# Voltage_Source.net
KiCad netlist of a schematic drawn in Altium Designer
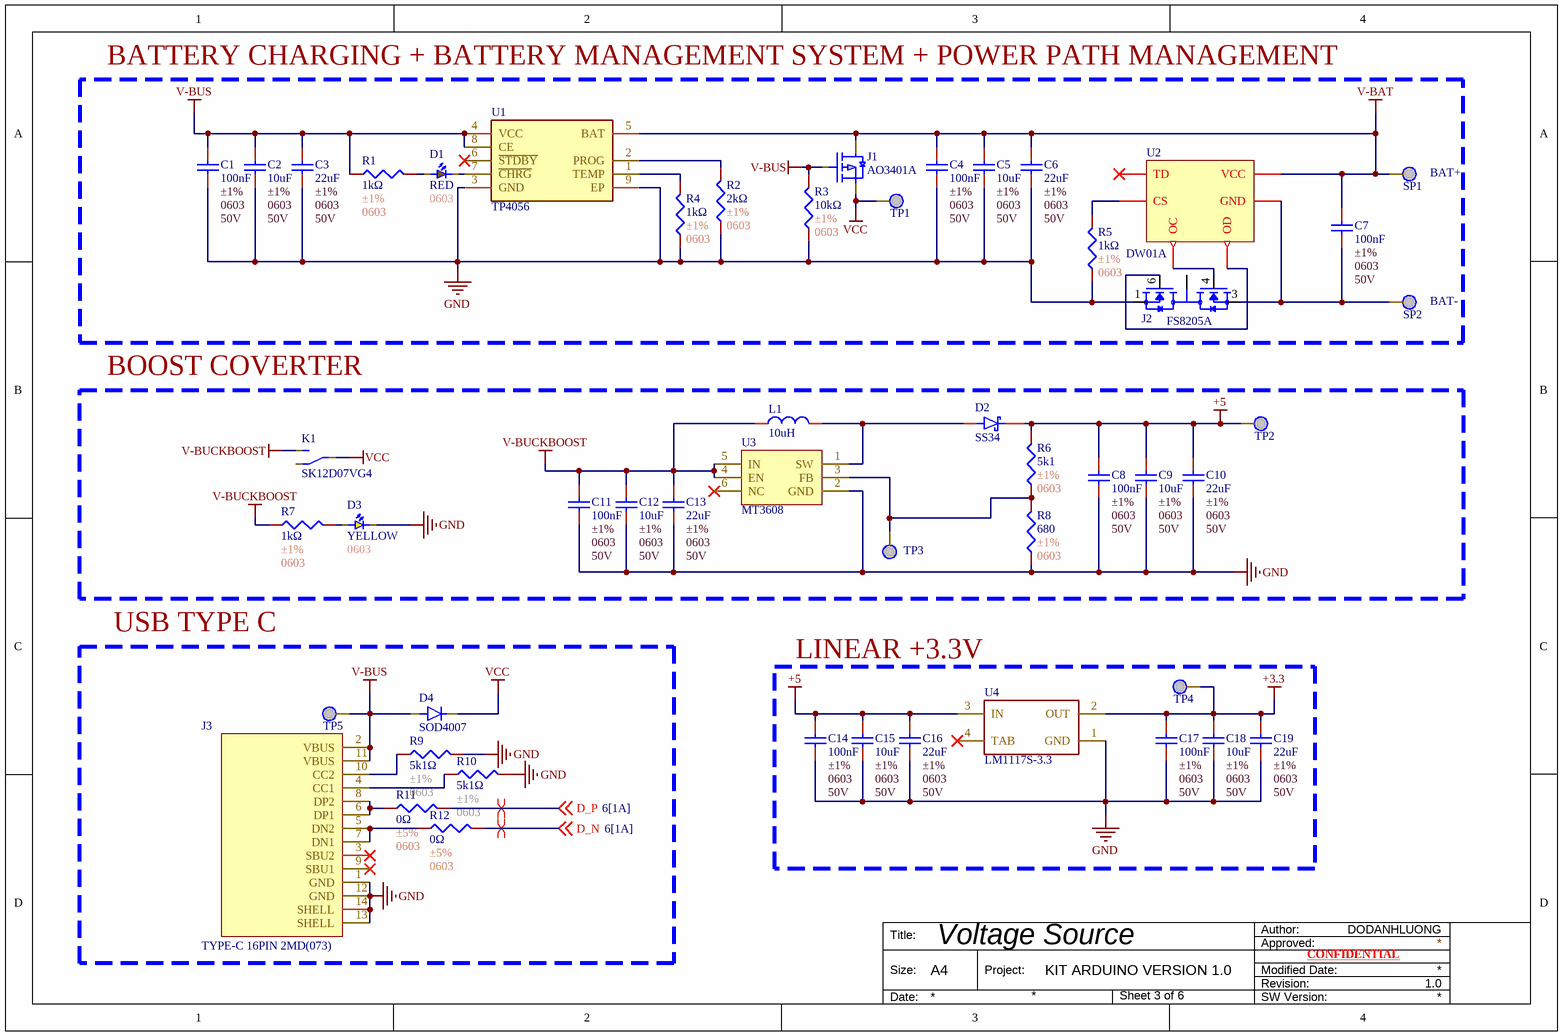
[diagram p0: Voltage Source.SchDoc]

(export (version "E")
  (design (tool "Eeschema 10.0.6"))
  (components
    (comp (ref "C1")
      (value "100nF")
      (footprint "C0603")
      (description "50V 10pF NP0 ±1% 0402 Multilayer Ceramic Capacitors MLCC - SMD/SMT ROHS")
      (fields
        (field (name "MANUFACTURER") "YAGEO")
        (field (name "MFR. PART #") "CC0402FRNPO9BN100")
        (field (name "TOLERANCE") "±1%")
        (field (name "PACKAGE") "0603")
        (field (name "VOLTAGE RATING") "50V")
      )
      (libsource (lib "Capital") (part "C0603_100nF_±1%"))
    )
    (comp (ref "C2")
      (value "10uF")
      (footprint "C0603")
      (description "50V 10pF NP0 ±1% 0402 Multilayer Ceramic Capacitors MLCC - SMD/SMT ROHS")
      (fields
        (field (name "MANUFACTURER") "YAGEO")
        (field (name "MFR. PART #") "CC0402FRNPO9BN100")
        (field (name "TOLERANCE") "±1%")
        (field (name "PACKAGE") "0603")
        (field (name "VOLTAGE RATING") "50V")
      )
      (libsource (lib "Capital") (part "C0603_10uF_±1%"))
    )
    (comp (ref "C3")
      (value "22uF")
      (footprint "C0603")
      (description "50V 10pF NP0 ±1% 0402 Multilayer Ceramic Capacitors MLCC - SMD/SMT ROHS")
      (fields
        (field (name "MANUFACTURER") "YAGEO")
        (field (name "MFR. PART #") "CC0402FRNPO9BN100")
        (field (name "TOLERANCE") "±1%")
        (field (name "PACKAGE") "0603")
        (field (name "VOLTAGE RATING") "50V")
      )
      (libsource (lib "Capital") (part "C0603_22uF_±1%"))
    )
    (comp (ref "C4")
      (value "100nF")
      (footprint "C0603")
      (description "50V 10pF NP0 ±1% 0402 Multilayer Ceramic Capacitors MLCC - SMD/SMT ROHS")
      (fields
        (field (name "MANUFACTURER") "YAGEO")
        (field (name "MFR. PART #") "CC0402FRNPO9BN100")
        (field (name "TOLERANCE") "±1%")
        (field (name "PACKAGE") "0603")
        (field (name "VOLTAGE RATING") "50V")
      )
      (libsource (lib "Capital") (part "C0603_100nF_±1%"))
    )
    (comp (ref "C5")
      (value "10uF")
      (footprint "C0603")
      (description "50V 10pF NP0 ±1% 0402 Multilayer Ceramic Capacitors MLCC - SMD/SMT ROHS")
      (fields
        (field (name "MANUFACTURER") "YAGEO")
        (field (name "MFR. PART #") "CC0402FRNPO9BN100")
        (field (name "TOLERANCE") "±1%")
        (field (name "PACKAGE") "0603")
        (field (name "VOLTAGE RATING") "50V")
      )
      (libsource (lib "Capital") (part "C0603_10uF_±1%"))
    )
    (comp (ref "C6")
      (value "22uF")
      (footprint "C0603")
      (description "50V 10pF NP0 ±1% 0402 Multilayer Ceramic Capacitors MLCC - SMD/SMT ROHS")
      (fields
        (field (name "MANUFACTURER") "YAGEO")
        (field (name "MFR. PART #") "CC0402FRNPO9BN100")
        (field (name "TOLERANCE") "±1%")
        (field (name "PACKAGE") "0603")
        (field (name "VOLTAGE RATING") "50V")
      )
      (libsource (lib "Capital") (part "C0603_22uF_±1%"))
    )
    (comp (ref "C7")
      (value "100nF")
      (footprint "C0603")
      (description "50V 10pF NP0 ±1% 0402 Multilayer Ceramic Capacitors MLCC - SMD/SMT ROHS")
      (fields
        (field (name "MANUFACTURER") "YAGEO")
        (field (name "MFR. PART #") "CC0402FRNPO9BN100")
        (field (name "TOLERANCE") "±1%")
        (field (name "PACKAGE") "0603")
        (field (name "VOLTAGE RATING") "50V")
      )
      (libsource (lib "Capital") (part "C0603_100nF_±1%"))
    )
    (comp (ref "C8")
      (value "100nF")
      (footprint "C0603")
      (description "50V 10pF NP0 ±1% 0402 Multilayer Ceramic Capacitors MLCC - SMD/SMT ROHS")
      (fields
        (field (name "MANUFACTURER") "YAGEO")
        (field (name "MFR. PART #") "CC0402FRNPO9BN100")
        (field (name "TOLERANCE") "±1%")
        (field (name "PACKAGE") "0603")
        (field (name "VOLTAGE RATING") "50V")
      )
      (libsource (lib "Capital") (part "C0603_100nF_±1%"))
    )
    (comp (ref "C9")
      (value "10uF")
      (footprint "C0603")
      (description "50V 10pF NP0 ±1% 0402 Multilayer Ceramic Capacitors MLCC - SMD/SMT ROHS")
      (fields
        (field (name "MANUFACTURER") "YAGEO")
        (field (name "MFR. PART #") "CC0402FRNPO9BN100")
        (field (name "TOLERANCE") "±1%")
        (field (name "PACKAGE") "0603")
        (field (name "VOLTAGE RATING") "50V")
      )
      (libsource (lib "Capital") (part "C0603_10uF_±1%"))
    )
    (comp (ref "C10")
      (value "22uF")
      (footprint "C0603")
      (description "50V 10pF NP0 ±1% 0402 Multilayer Ceramic Capacitors MLCC - SMD/SMT ROHS")
      (fields
        (field (name "MANUFACTURER") "YAGEO")
        (field (name "MFR. PART #") "CC0402FRNPO9BN100")
        (field (name "TOLERANCE") "±1%")
        (field (name "PACKAGE") "0603")
        (field (name "VOLTAGE RATING") "50V")
      )
      (libsource (lib "Capital") (part "C0603_22uF_±1%"))
    )
    (comp (ref "C11")
      (value "100nF")
      (footprint "C0603")
      (description "50V 10pF NP0 ±1% 0402 Multilayer Ceramic Capacitors MLCC - SMD/SMT ROHS")
      (fields
        (field (name "MANUFACTURER") "YAGEO")
        (field (name "MFR. PART #") "CC0402FRNPO9BN100")
        (field (name "TOLERANCE") "±1%")
        (field (name "PACKAGE") "0603")
        (field (name "VOLTAGE RATING") "50V")
      )
      (libsource (lib "Capital") (part "C0603_100nF_±1%"))
    )
    (comp (ref "C12")
      (value "10uF")
      (footprint "C0603")
      (description "50V 10pF NP0 ±1% 0402 Multilayer Ceramic Capacitors MLCC - SMD/SMT ROHS")
      (fields
        (field (name "MANUFACTURER") "YAGEO")
        (field (name "MFR. PART #") "CC0402FRNPO9BN100")
        (field (name "TOLERANCE") "±1%")
        (field (name "PACKAGE") "0603")
        (field (name "VOLTAGE RATING") "50V")
      )
      (libsource (lib "Capital") (part "C0603_10uF_±1%"))
    )
    (comp (ref "C13")
      (value "22uF")
      (footprint "C0603")
      (description "50V 10pF NP0 ±1% 0402 Multilayer Ceramic Capacitors MLCC - SMD/SMT ROHS")
      (fields
        (field (name "MANUFACTURER") "YAGEO")
        (field (name "MFR. PART #") "CC0402FRNPO9BN100")
        (field (name "TOLERANCE") "±1%")
        (field (name "PACKAGE") "0603")
        (field (name "VOLTAGE RATING") "50V")
      )
      (libsource (lib "Capital") (part "C0603_22uF_±1%"))
    )
    (comp (ref "C14")
      (value "100nF")
      (footprint "C0603")
      (description "50V 10pF NP0 ±1% 0402 Multilayer Ceramic Capacitors MLCC - SMD/SMT ROHS")
      (fields
        (field (name "MANUFACTURER") "YAGEO")
        (field (name "MFR. PART #") "CC0402FRNPO9BN100")
        (field (name "TOLERANCE") "±1%")
        (field (name "PACKAGE") "0603")
        (field (name "VOLTAGE RATING") "50V")
      )
      (libsource (lib "Capital") (part "C0603_100nF_±1%"))
    )
    (comp (ref "C15")
      (value "10uF")
      (footprint "C0603")
      (description "50V 10pF NP0 ±1% 0402 Multilayer Ceramic Capacitors MLCC - SMD/SMT ROHS")
      (fields
        (field (name "MANUFACTURER") "YAGEO")
        (field (name "MFR. PART #") "CC0402FRNPO9BN100")
        (field (name "TOLERANCE") "±1%")
        (field (name "PACKAGE") "0603")
        (field (name "VOLTAGE RATING") "50V")
      )
      (libsource (lib "Capital") (part "C0603_10uF_±1%"))
    )
    (comp (ref "C16")
      (value "22uF")
      (footprint "C0603")
      (description "50V 10pF NP0 ±1% 0402 Multilayer Ceramic Capacitors MLCC - SMD/SMT ROHS")
      (fields
        (field (name "MANUFACTURER") "YAGEO")
        (field (name "MFR. PART #") "CC0402FRNPO9BN100")
        (field (name "TOLERANCE") "±1%")
        (field (name "PACKAGE") "0603")
        (field (name "VOLTAGE RATING") "50V")
      )
      (libsource (lib "Capital") (part "C0603_22uF_±1%"))
    )
    (comp (ref "C17")
      (value "100nF")
      (footprint "C0603")
      (description "50V 10pF NP0 ±1% 0402 Multilayer Ceramic Capacitors MLCC - SMD/SMT ROHS")
      (fields
        (field (name "MANUFACTURER") "YAGEO")
        (field (name "MFR. PART #") "CC0402FRNPO9BN100")
        (field (name "TOLERANCE") "±1%")
        (field (name "PACKAGE") "0603")
        (field (name "VOLTAGE RATING") "50V")
      )
      (libsource (lib "Capital") (part "C0603_100nF_±1%"))
    )
    (comp (ref "C18")
      (value "10uF")
      (footprint "C0603")
      (description "50V 10pF NP0 ±1% 0402 Multilayer Ceramic Capacitors MLCC - SMD/SMT ROHS")
      (fields
        (field (name "MANUFACTURER") "YAGEO")
        (field (name "MFR. PART #") "CC0402FRNPO9BN100")
        (field (name "TOLERANCE") "±1%")
        (field (name "PACKAGE") "0603")
        (field (name "VOLTAGE RATING") "50V")
      )
      (libsource (lib "Capital") (part "C0603_10uF_±1%"))
    )
    (comp (ref "C19")
      (value "22uF")
      (footprint "C0603")
      (description "50V 10pF NP0 ±1% 0402 Multilayer Ceramic Capacitors MLCC - SMD/SMT ROHS")
      (fields
        (field (name "MANUFACTURER") "YAGEO")
        (field (name "MFR. PART #") "CC0402FRNPO9BN100")
        (field (name "TOLERANCE") "±1%")
        (field (name "PACKAGE") "0603")
        (field (name "VOLTAGE RATING") "50V")
      )
      (libsource (lib "Capital") (part "C0603_22uF_±1%"))
    )
    (comp (ref "D1")
      (value "RED")
      (footprint "LED0603")
      (description "25mcd~40mcd Water Clear -40℃~+85℃ 624nm Red 120° 60mW 0402 LED Indication - Discrete ROHS")
      (fields
        (field (name "MANUFACTURER") "XINGLIGHT")
        (field (name "MFR. PART #") "XL-1005UGC")
        (field (name "PACKAGE") "0603")
      )
      (libsource (lib "LED") (part "D0603_RED"))
    )
    (comp (ref "D2")
      (value "SS34")
      (footprint "SS34")
      (description "40V Independent 3A 550mV@3A SMA(DO-214AC) Schottky Diodes ROHS")
      (fields
        (field (name "MANUFACTURER") "MDD(Microdiode Semiconductor)")
        (field (name "LCSC PART #") "C8678")
      )
      (libsource (lib "Diode") (part "SS34"))
    )
    (comp (ref "D3")
      (value "YELLOW")
      (footprint "LED0603")
      (description "25mcd~40mcd Water Clear -40℃~+85℃ 624nm Red 120° 60mW 0402 LED Indication - Discrete ROHS")
      (fields
        (field (name "MANUFACTURER") "XINGLIGHT")
        (field (name "MFR. PART #") "XL-1005UGC")
        (field (name "PACKAGE") "0603")
      )
      (libsource (lib "LED") (part "D0603_YELLOW"))
    )
    (comp (ref "D4")
      (value "SOD4007")
      (footprint "SOD4007")
      (description "1A Independent 1kV 1.1V@1A SOD-123FL Diodes - General Purpose ROHS")
      (fields
        (field (name "MANUFACTURER") "MDD(Microdiode Semiconductor)")
        (field (name "LCSC PART #") "C18124")
      )
      (libsource (lib "Diode") (part "SOD4007"))
    )
    (comp (ref "J1")
      (value "AO3401A")
      (footprint "AO3401A")
      (description "30V 4A 900mV@250uA 1 P-Channel SOT-23 MOSFETs ROHS")
      (fields (field (name "MANUFACTURER") "AOS") (field (name "LCSC PART #") "C15127"))
      (libsource (lib "Mosfet") (part "AO3401"))
    )
    (comp (ref "J2")
      (value "FS8205A")
      (footprint "FS8205A")
      (description "20V 9A 31.5mΩ@2.5V 1.5W 1.2V@250uA SOT-23-6 MOSFETs ROHS")
      (fields (field (name "MANUFACTURER") "TECH PUBLIC") (field (name "LCSC PART #") "C2830320"))
      (libsource (lib "IC") (part "FS8205A"))
    )
    (comp (ref "J3")
      (value "TYPE-C 16PIN 2MD(073)")
      (footprint "TYPE_C_FAMALE")
      (description "3A 1 Surface Mount, Right Angle 16P Female -25℃~+85℃ Type-C SMD USB Connectors ROHS")
      (fields (field (name "MANUFACTURER") "SHOU HAN") (field (name "LCSC PART #") "C2765186"))
      (libsource (lib "Connector") (part "TYPE_C_FAMALE_16PIN"))
    )
    (comp (ref "K1")
      (value "SK12D07VG4")
      (footprint "SK12D07VG4")
      (description "500mA SPDT 50V 5,000 Cycles Through Hole Slide Switches ROHS")
      (fields (field (name "MANUFACTURER") "SHOU HAN") (field (name "LCSC PART #") "C393937"))
      (libsource (lib "Switch") (part "SK12D07VG4"))
    )
    (comp (ref "L1")
      (value "10uH")
      (footprint "CD43")
      (description "1.15A 10uH Unshielded Inductor ±20% SMD,4x4.5mm Power Inductors ROHS")
      (fields (field (name "MANUFACTURER") "ZE") (field (name "MFR. PART #") "CD43-100M"))
      (libsource (lib "Inductor") (part "CD4-10UH"))
    )
    (comp (ref "R1")
      (value "1kΩ")
      (footprint "R0603")
      (description "62.5mW Thick Film Resistor 50V ±1% ±200ppm/℃ 10Ω 0402 Chip Resistor - Surface Mount ROHS")
      (fields
        (field (name "MANUFACTURER") "YAGEO")
        (field (name "MFR. PART #") "RC0402FR-0710RL")
        (field (name "TOLERANCE") "±1%")
        (field (name "PACKAGE") "0603")
      )
      (libsource (lib "Resistor") (part "R0603_1kΩ_±1%"))
    )
    (comp (ref "R2")
      (value "2kΩ")
      (footprint "R0603")
      (description "62.5mW Thick Film Resistor 50V ±1% ±200ppm/℃ 10Ω 0402 Chip Resistor - Surface Mount ROHS")
      (fields
        (field (name "MANUFACTURER") "YAGEO")
        (field (name "MFR. PART #") "RC0402FR-0710RL")
        (field (name "TOLERANCE") "±1%")
        (field (name "PACKAGE") "0603")
      )
      (libsource (lib "Resistor") (part "R0603_2kΩ_±1%"))
    )
    (comp (ref "R3")
      (value "10kΩ")
      (footprint "R0603")
      (description "62.5mW Thick Film Resistor 50V ±1% ±200ppm/℃ 10Ω 0402 Chip Resistor - Surface Mount ROHS")
      (fields
        (field (name "MANUFACTURER") "YAGEO")
        (field (name "MFR. PART #") "RC0402FR-0710RL")
        (field (name "TOLERANCE") "±1%")
        (field (name "PACKAGE") "0603")
      )
      (libsource (lib "Resistor") (part "R0603_10kΩ_±1%"))
    )
    (comp (ref "R4")
      (value "1kΩ")
      (footprint "R0603")
      (description "62.5mW Thick Film Resistor 50V ±1% ±200ppm/℃ 10Ω 0402 Chip Resistor - Surface Mount ROHS")
      (fields
        (field (name "MANUFACTURER") "YAGEO")
        (field (name "MFR. PART #") "RC0402FR-0710RL")
        (field (name "TOLERANCE") "±1%")
        (field (name "PACKAGE") "0603")
      )
      (libsource (lib "Resistor") (part "R0603_1kΩ_±1%"))
    )
    (comp (ref "R5")
      (value "1kΩ")
      (footprint "R0603")
      (description "62.5mW Thick Film Resistor 50V ±1% ±200ppm/℃ 10Ω 0402 Chip Resistor - Surface Mount ROHS")
      (fields
        (field (name "MANUFACTURER") "YAGEO")
        (field (name "MFR. PART #") "RC0402FR-0710RL")
        (field (name "TOLERANCE") "±1%")
        (field (name "PACKAGE") "0603")
      )
      (libsource (lib "Resistor") (part "R0603_1kΩ_±1%"))
    )
    (comp (ref "R6")
      (value "5k1")
      (footprint "R0603")
      (description "62.5mW Thick Film Resistor 50V ±1% ±200ppm/℃ 10Ω 0402 Chip Resistor - Surface Mount ROHS")
      (fields
        (field (name "MANUFACTURER") "YAGEO")
        (field (name "MFR. PART #") "RC0402FR-0710RL")
        (field (name "TOLERANCE") "±1%")
        (field (name "PACKAGE") "0603")
      )
      (libsource (lib "Resistor") (part "R0603_10kΩ_±1%"))
    )
    (comp (ref "R7")
      (value "1kΩ")
      (footprint "R0603")
      (description "62.5mW Thick Film Resistor 50V ±1% ±200ppm/℃ 10Ω 0402 Chip Resistor - Surface Mount ROHS")
      (fields
        (field (name "MANUFACTURER") "YAGEO")
        (field (name "MFR. PART #") "RC0402FR-0710RL")
        (field (name "TOLERANCE") "±1%")
        (field (name "PACKAGE") "0603")
      )
      (libsource (lib "Resistor") (part "R0603_1kΩ_±1%"))
    )
    (comp (ref "R8")
      (value "680")
      (footprint "R0603")
      (description "62.5mW Thick Film Resistor 50V ±1% ±200ppm/℃ 10Ω 0402 Chip Resistor - Surface Mount ROHS")
      (fields
        (field (name "MANUFACTURER") "YAGEO")
        (field (name "MFR. PART #") "RC0402FR-0710RL")
        (field (name "TOLERANCE") "±1%")
        (field (name "PACKAGE") "0603")
      )
      (libsource (lib "Resistor") (part "R0603_2kΩ_±1%"))
    )
    (comp (ref "R9")
      (value "5k1Ω")
      (footprint "R0603")
      (description "100mW Thick Film Resistor 75V ±100ppm/℃ ±1% 5.1kΩ 0603 Chip Resistor - Surface Mount ROHS")
      (fields
        (field (name "MANUFACTURER") "FOJAN")
        (field (name "MFR. PART #") "FRC0603F5101TS")
        (field (name "TOLERANCE") "±1%")
        (field (name "PACKAGE") "0603")
      )
      (libsource (lib "Resistor") (part "R0603_5k1Ω_±1%"))
    )
    (comp (ref "R10")
      (value "5k1Ω")
      (footprint "R0603")
      (description "100mW Thick Film Resistor 75V ±100ppm/℃ ±1% 5.1kΩ 0603 Chip Resistor - Surface Mount ROHS")
      (fields
        (field (name "MANUFACTURER") "FOJAN")
        (field (name "MFR. PART #") "FRC0603F5101TS")
        (field (name "TOLERANCE") "±1%")
        (field (name "PACKAGE") "0603")
      )
      (libsource (lib "Resistor") (part "R0603_5k1Ω_±1%"))
    )
    (comp (ref "R11")
      (value "0Ω")
      (footprint "R0603")
      (description "100mW Thick Film Resistor 75V ±5% 0Ω 0603 Chip Resistor - Surface Mount ROHS")
      (fields
        (field (name "MANUFACTURER") "YAGEO")
        (field (name "MFR. PART #") "RC0603JR-070RL")
        (field (name "TOLERANCE") "±5%")
        (field (name "PACKAGE") "0603")
      )
      (libsource (lib "Resistor") (part "R0603_0Ω_±5%"))
    )
    (comp (ref "R12")
      (value "0Ω")
      (footprint "R0603")
      (description "100mW Thick Film Resistor 75V ±5% 0Ω 0603 Chip Resistor - Surface Mount ROHS")
      (fields
        (field (name "MANUFACTURER") "YAGEO")
        (field (name "MFR. PART #") "RC0603JR-070RL")
        (field (name "TOLERANCE") "±5%")
        (field (name "PACKAGE") "0603")
      )
      (libsource (lib "Resistor") (part "R0603_0Ω_±5%"))
    )
    (comp (ref "SP1") (value "BAT+") (footprint "SP") (libsource (lib "Other") (part "SP")))
    (comp (ref "SP2") (value "BAT-") (footprint "SP") (libsource (lib "Other") (part "SP")))
    (comp (ref "TP1") (value "TP") (footprint "TP") (libsource (lib "Other") (part "TP")))
    (comp (ref "TP2") (value "TP") (footprint "TP") (libsource (lib "Other") (part "TP")))
    (comp (ref "TP3") (value "TP") (footprint "TP") (libsource (lib "Other") (part "TP")))
    (comp (ref "TP4") (value "TP") (footprint "TP") (libsource (lib "Other") (part "TP")))
    (comp (ref "TP5") (value "TP") (footprint "TP") (libsource (lib "Other") (part "TP")))
    (comp (ref "U1")
      (value "TP4056")
      (footprint "TP4056")
      (description "4V~6V Lithium-ion/Polymer 1 ESOP-8 Battery Management ROHS")
      (fields (field (name "MANUFACTURER") "TPOWER") (field (name "LCSC PART #") "C382139"))
      (libsource (lib "IC") (part "TP4056"))
    )
    (comp (ref "U2")
      (value "DW01A")
      (footprint "DW01A")
      (description "1.5V~8V Lithium-ion/Polymer 1 SOT-23-6 Battery Management ROHS")
      (fields (field (name "MANUFACTURER") "YONGYUTAI") (field (name "LCSC PART #") "C2927799"))
      (libsource (lib "IC") (part "DW01A"))
    )
    (comp (ref "U3")
      (value "MT3608")
      (footprint "MT3608")
      (description "Boost Adjustable 2A 2V~24V SOT-23-6 DC-DC Converters ROHS")
      (fields (field (name "MANUFACTURER") "XI'AN Aerosemi Tech") (field (name "LCSC PART #") "C84817"))
      (libsource (lib "IC") (part "MT3608"))
    )
    (comp (ref "U4")
      (value "LM1117S-3.3")
      (footprint "AMS1117-3.3")
      (fields (field (name "MANUFACTURER") "HTC") (field (name "LCSC PART #") "C126027"))
      (libsource (lib "IC") (part "LM1117S-3.3"))
    )
  )
  (nets
    (net (code "1") (name "+3.3") (class "Default")
      (node (ref "C17") (pin "1") (pinfunction "1_1") (pintype "passive"))
      (node (ref "C18") (pin "1") (pinfunction "1_1") (pintype "passive"))
      (node (ref "C19") (pin "1") (pinfunction "1_1") (pintype "passive"))
      (node (ref "TP4") (pin "1") (pinfunction "1_1") (pintype "passive"))
      (node (ref "U4") (pin "2") (pinfunction "OUT_2") (pintype "passive"))
    )
    (net (code "2") (name "+5") (class "Default")
      (node (ref "C10") (pin "1") (pinfunction "1_1") (pintype "passive"))
      (node (ref "C14") (pin "1") (pinfunction "1_1") (pintype "passive"))
      (node (ref "C15") (pin "1") (pinfunction "1_1") (pintype "passive"))
      (node (ref "C16") (pin "1") (pinfunction "1_1") (pintype "passive"))
      (node (ref "C8") (pin "1") (pinfunction "1_1") (pintype "passive"))
      (node (ref "C9") (pin "1") (pinfunction "1_1") (pintype "passive"))
      (node (ref "D2") (pin "1") (pinfunction "1_1") (pintype "passive"))
      (node (ref "R6") (pin "2") (pinfunction "2_2") (pintype "passive"))
      (node (ref "TP2") (pin "1") (pinfunction "1_1") (pintype "passive"))
      (node (ref "U4") (pin "3") (pinfunction "IN_3") (pintype "passive"))
    )
    (net (code "3") (name "D_N") (class "Default")
      (node (ref "R12") (pin "2") (pinfunction "2_2") (pintype "passive"))
    )
    (net (code "4") (name "D_P") (class "Default")
      (node (ref "R11") (pin "2") (pinfunction "2_2") (pintype "passive"))
    )
    (net (code "5") (name "GND") (class "Default")
      (node (ref "C1") (pin "2") (pinfunction "2_2") (pintype "passive"))
      (node (ref "C10") (pin "2") (pinfunction "2_2") (pintype "passive"))
      (node (ref "C11") (pin "2") (pinfunction "2_2") (pintype "passive"))
      (node (ref "C12") (pin "2") (pinfunction "2_2") (pintype "passive"))
      (node (ref "C13") (pin "2") (pinfunction "2_2") (pintype "passive"))
      (node (ref "C14") (pin "2") (pinfunction "2_2") (pintype "passive"))
      (node (ref "C15") (pin "2") (pinfunction "2_2") (pintype "passive"))
      (node (ref "C16") (pin "2") (pinfunction "2_2") (pintype "passive"))
      (node (ref "C17") (pin "2") (pinfunction "2_2") (pintype "passive"))
      (node (ref "C18") (pin "2") (pinfunction "2_2") (pintype "passive"))
      (node (ref "C19") (pin "2") (pinfunction "2_2") (pintype "passive"))
      (node (ref "C2") (pin "2") (pinfunction "2_2") (pintype "passive"))
      (node (ref "C3") (pin "2") (pinfunction "2_2") (pintype "passive"))
      (node (ref "C4") (pin "2") (pinfunction "2_2") (pintype "passive"))
      (node (ref "C5") (pin "2") (pinfunction "2_2") (pintype "passive"))
      (node (ref "C6") (pin "2") (pinfunction "2_2") (pintype "passive"))
      (node (ref "C8") (pin "2") (pinfunction "2_2") (pintype "passive"))
      (node (ref "C9") (pin "2") (pinfunction "2_2") (pintype "passive"))
      (node (ref "D3") (pin "1") (pinfunction "1_1") (pintype "passive"))
      (node (ref "J2") (pin "1") (pinfunction "S1_1") (pintype "passive"))
      (node (ref "J3") (pin "1") (pinfunction "GND_1") (pintype "passive"))
      (node (ref "J3") (pin "12") (pinfunction "GND_12") (pintype "passive"))
      (node (ref "J3") (pin "13") (pinfunction "SHELL_13") (pintype "passive"))
      (node (ref "J3") (pin "14") (pinfunction "SHELL_14") (pintype "passive"))
      (node (ref "R10") (pin "2") (pinfunction "2_2") (pintype "passive"))
      (node (ref "R2") (pin "1") (pinfunction "1_1") (pintype "passive"))
      (node (ref "R3") (pin "1") (pinfunction "1_1") (pintype "passive"))
      (node (ref "R4") (pin "1") (pinfunction "1_1") (pintype "passive"))
      (node (ref "R5") (pin "1") (pinfunction "1_1") (pintype "passive"))
      (node (ref "R8") (pin "1") (pinfunction "1_1") (pintype "passive"))
      (node (ref "R9") (pin "2") (pinfunction "2_2") (pintype "passive"))
      (node (ref "U1") (pin "3") (pinfunction "GND_3") (pintype "passive"))
      (node (ref "U1") (pin "9") (pinfunction "EP_9") (pintype "passive"))
      (node (ref "U3") (pin "2") (pinfunction "GND_2") (pintype "passive"))
      (node (ref "U4") (pin "1") (pinfunction "GND_1") (pintype "passive"))
    )
    (net (code "6") (name "Net-(D1-Pad2)") (class "Default")
      (node (ref "D1") (pin "2") (pinfunction "2_2") (pintype "passive"))
      (node (ref "R1") (pin "2") (pinfunction "2_2") (pintype "passive"))
    )
    (net (code "7") (name "Net-(D3-Pad2)") (class "Default")
      (node (ref "D3") (pin "2") (pinfunction "2_2") (pintype "passive"))
      (node (ref "R7") (pin "2") (pinfunction "2_2") (pintype "passive"))
    )
    (net (code "8") (name "Net-(J2-D12-Pad2)") (class "Default")
      (node (ref "J2") (pin "2") (pinfunction "D12_2") (pintype "passive"))
      (node (ref "J2") (pin "5") (pinfunction "D12_5") (pintype "passive"))
    )
    (net (code "9") (name "Net-(J2-G1)") (class "Default")
      (node (ref "J2") (pin "6") (pinfunction "G1_6") (pintype "passive"))
      (node (ref "U2") (pin "1") (pinfunction "OD_1") (pintype "output"))
    )
    (net (code "10") (name "Net-(J2-G2)") (class "Default")
      (node (ref "J2") (pin "4") (pinfunction "G2_4") (pintype "passive"))
      (node (ref "U2") (pin "3") (pinfunction "OC_3") (pintype "output"))
    )
    (net (code "11") (name "Net-(J2-S2)") (class "Default")
      (node (ref "C7") (pin "2") (pinfunction "2_2") (pintype "passive"))
      (node (ref "J2") (pin "3") (pinfunction "S2_3") (pintype "passive"))
      (node (ref "SP2") (pin "1") (pinfunction "1_1") (pintype "passive"))
      (node (ref "U2") (pin "6") (pinfunction "GND_6") (pintype "passive"))
    )
    (net (code "12") (name "Net-(J3-CC1)") (class "Default")
      (node (ref "J3") (pin "4") (pinfunction "CC1_4") (pintype "passive"))
      (node (ref "R10") (pin "1") (pinfunction "1_1") (pintype "passive"))
    )
    (net (code "13") (name "Net-(J3-CC2)") (class "Default")
      (node (ref "J3") (pin "10") (pinfunction "CC2_10") (pintype "passive"))
      (node (ref "R9") (pin "1") (pinfunction "1_1") (pintype "passive"))
    )
    (net (code "14") (name "Net-(J3-DN1)") (class "Default")
      (node (ref "J3") (pin "5") (pinfunction "DN2_5") (pintype "passive"))
      (node (ref "J3") (pin "7") (pinfunction "DN1_7") (pintype "passive"))
      (node (ref "R12") (pin "1") (pinfunction "1_1") (pintype "passive"))
    )
    (net (code "15") (name "Net-(J3-DP1)") (class "Default")
      (node (ref "J3") (pin "6") (pinfunction "DP1_6") (pintype "passive"))
      (node (ref "J3") (pin "8") (pinfunction "DP2_8") (pintype "passive"))
      (node (ref "R11") (pin "1") (pinfunction "1_1") (pintype "passive"))
    )
    (net (code "16") (name "Net-(U1-PROG)") (class "Default")
      (node (ref "R2") (pin "2") (pinfunction "2_2") (pintype "passive"))
      (node (ref "U1") (pin "2") (pinfunction "PROG_2") (pintype "passive"))
    )
    (net (code "17") (name "Net-(U1-TEMP)") (class "Default")
      (node (ref "R4") (pin "2") (pinfunction "2_2") (pintype "passive"))
      (node (ref "U1") (pin "1") (pinfunction "TEMP_1") (pintype "passive"))
    )
    (net (code "18") (name "Net-(U1-~{CHRG})") (class "Default")
      (node (ref "D1") (pin "1") (pinfunction "1_1") (pintype "passive"))
      (node (ref "U1") (pin "7") (pinfunction "~{CHRG}_7") (pintype "passive"))
    )
    (net (code "19") (name "Net-(U2-CS)") (class "Default")
      (node (ref "R5") (pin "2") (pinfunction "2_2") (pintype "passive"))
      (node (ref "U2") (pin "2") (pinfunction "CS_2") (pintype "passive"))
    )
    (net (code "20") (name "Net-(U3-FB)") (class "Default")
      (node (ref "R6") (pin "1") (pinfunction "1_1") (pintype "passive"))
      (node (ref "R8") (pin "2") (pinfunction "2_2") (pintype "passive"))
      (node (ref "TP3") (pin "1") (pinfunction "1_1") (pintype "passive"))
      (node (ref "U3") (pin "3") (pinfunction "FB_3") (pintype "passive"))
    )
    (net (code "21") (name "Net-(U3-SW)") (class "Default")
      (node (ref "D2") (pin "2") (pinfunction "2_2") (pintype "passive"))
      (node (ref "L1") (pin "2") (pinfunction "2_2") (pintype "passive"))
      (node (ref "U3") (pin "1") (pinfunction "SW_1") (pintype "passive"))
    )
    (net (code "22") (name "V-BAT") (class "Default")
      (node (ref "C4") (pin "1") (pinfunction "1_1") (pintype "passive"))
      (node (ref "C5") (pin "1") (pinfunction "1_1") (pintype "passive"))
      (node (ref "C6") (pin "1") (pinfunction "1_1") (pintype "passive"))
      (node (ref "C7") (pin "1") (pinfunction "1_1") (pintype "passive"))
      (node (ref "J1") (pin "3") (pinfunction "D_3") (pintype "passive"))
      (node (ref "SP1") (pin "1") (pinfunction "1_1") (pintype "passive"))
      (node (ref "U1") (pin "5") (pinfunction "BAT_5") (pintype "passive"))
      (node (ref "U2") (pin "5") (pinfunction "VCC_5") (pintype "passive"))
    )
    (net (code "23") (name "V-BUCKBOOST") (class "Default")
      (node (ref "C11") (pin "1") (pinfunction "1_1") (pintype "passive"))
      (node (ref "C12") (pin "1") (pinfunction "1_1") (pintype "passive"))
      (node (ref "C13") (pin "1") (pinfunction "1_1") (pintype "passive"))
      (node (ref "K1") (pin "1") (pinfunction "1_1") (pintype "passive"))
      (node (ref "L1") (pin "1") (pinfunction "1_1") (pintype "passive"))
      (node (ref "R7") (pin "1") (pinfunction "1_1") (pintype "passive"))
      (node (ref "U3") (pin "4") (pinfunction "EN_4") (pintype "passive"))
      (node (ref "U3") (pin "5") (pinfunction "IN_5") (pintype "passive"))
    )
    (net (code "24") (name "V-BUS") (class "Default")
      (node (ref "C1") (pin "1") (pinfunction "1_1") (pintype "passive"))
      (node (ref "C2") (pin "1") (pinfunction "1_1") (pintype "passive"))
      (node (ref "C3") (pin "1") (pinfunction "1_1") (pintype "passive"))
      (node (ref "D4") (pin "2") (pinfunction "A_2") (pintype "passive"))
      (node (ref "J1") (pin "1") (pinfunction "G_1") (pintype "passive"))
      (node (ref "J3") (pin "11") (pinfunction "VBUS_11") (pintype "passive"))
      (node (ref "J3") (pin "2") (pinfunction "VBUS_2") (pintype "passive"))
      (node (ref "R1") (pin "1") (pinfunction "1_1") (pintype "passive"))
      (node (ref "R3") (pin "2") (pinfunction "2_2") (pintype "passive"))
      (node (ref "TP5") (pin "1") (pinfunction "1_1") (pintype "passive"))
      (node (ref "U1") (pin "4") (pinfunction "VCC_4") (pintype "passive"))
      (node (ref "U1") (pin "8") (pinfunction "CE_8") (pintype "passive"))
    )
    (net (code "25") (name "VCC") (class "Default")
      (node (ref "D4") (pin "1") (pinfunction "C_1") (pintype "passive"))
      (node (ref "J1") (pin "2") (pinfunction "S_2") (pintype "passive"))
      (node (ref "K1") (pin "2") (pinfunction "2_2") (pintype "passive"))
      (node (ref "TP1") (pin "1") (pinfunction "1_1") (pintype "passive"))
    )
    (net (code "26") (name "unconnected-(J3-SBU1-Pad9)") (class "Default")
      (node (ref "J3") (pin "9") (pinfunction "SBU1_9") (pintype "passive+no_connect"))
    )
    (net (code "27") (name "unconnected-(J3-SBU2-Pad3)") (class "Default")
      (node (ref "J3") (pin "3") (pinfunction "SBU2_3") (pintype "passive+no_connect"))
    )
    (net (code "28") (name "unconnected-(K1-Pad3)") (class "Default")
      (node (ref "K1") (pin "3") (pinfunction "3_3") (pintype "passive"))
    )
    (net (code "29") (name "unconnected-(U1-~{STDBY}-Pad6)") (class "Default")
      (node (ref "U1") (pin "6") (pinfunction "~{STDBY}_6") (pintype "passive+no_connect"))
    )
    (net (code "30") (name "unconnected-(U2-TD-Pad4)") (class "Default")
      (node (ref "U2") (pin "4") (pinfunction "TD_4") (pintype "passive+no_connect"))
    )
    (net (code "31") (name "unconnected-(U3-NC-Pad6)") (class "Default")
      (node (ref "U3") (pin "6") (pinfunction "NC_6") (pintype "passive+no_connect"))
    )
    (net (code "32") (name "unconnected-(U4-TAB-Pad4)") (class "Default")
      (node (ref "U4") (pin "4") (pinfunction "TAB_4") (pintype "passive+no_connect"))
    )
  )
)
